# Sunrise.net
KiCad netlist of a schematic drawn in EAGLE
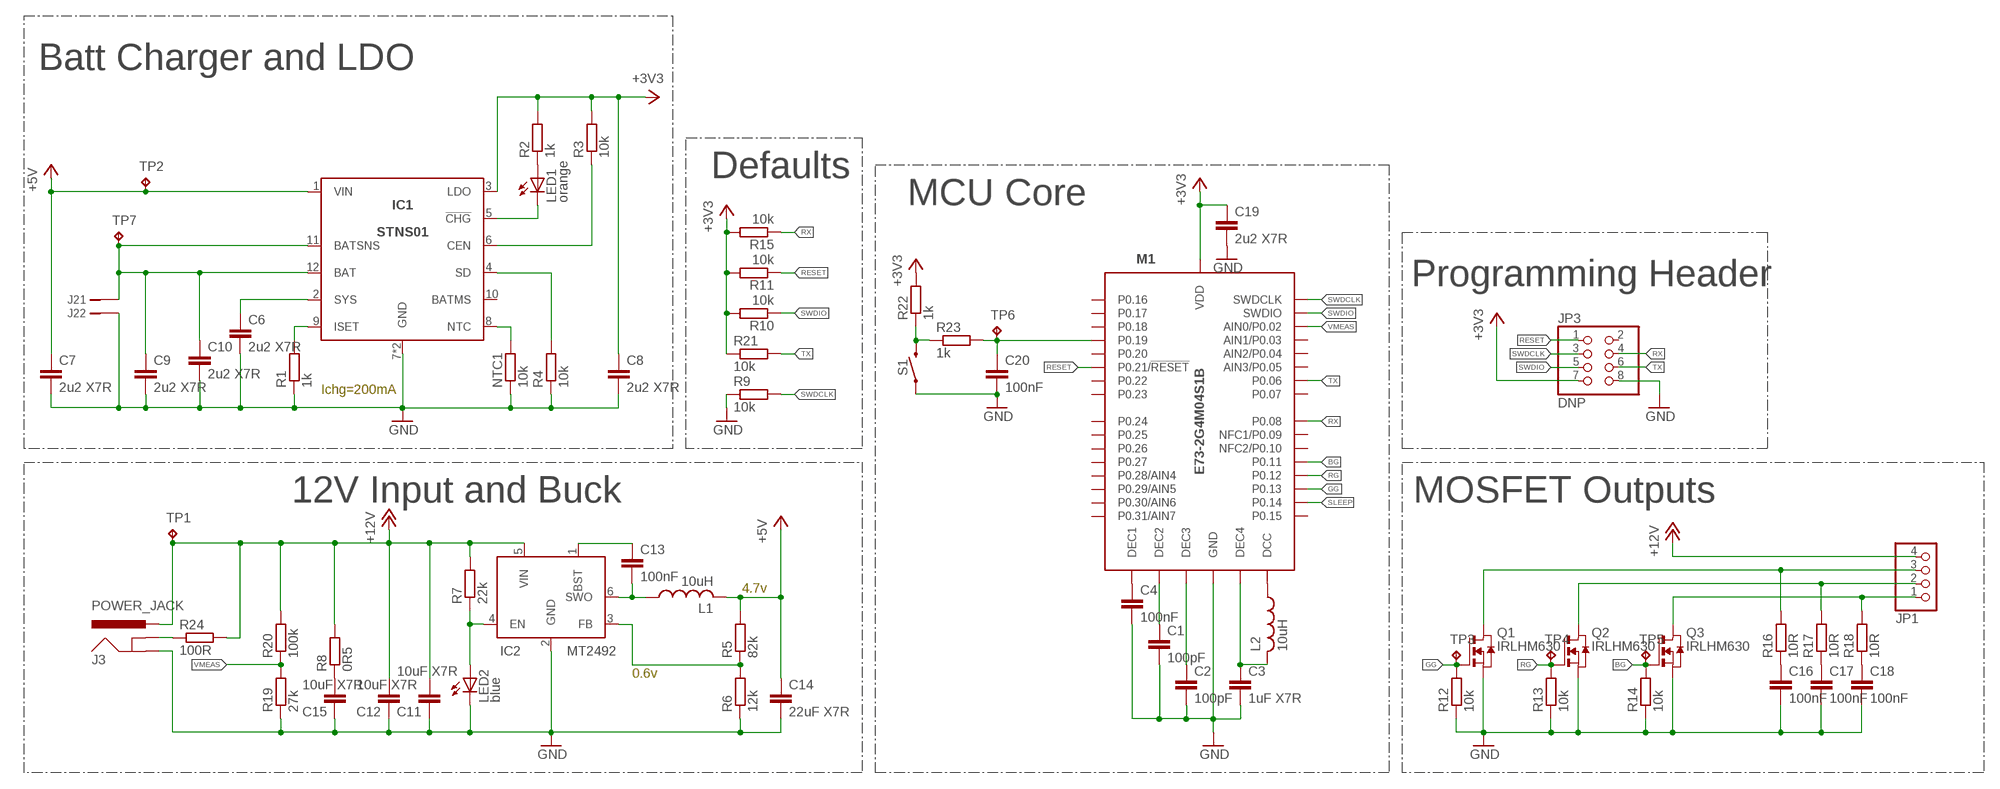
[diagram p0: schematic, sheet 1]

(export (version "E")
  (design (tool "Eeschema 10.0.6"))
  (components
    (comp (ref "C1")
      (value "100pF")
      (footprint "eagle-import:C0402K")
      (libsource (lib "eagle-import") (part "C-EUC0402K"))
    )
    (comp (ref "C2")
      (value "100pF")
      (footprint "eagle-import:C0402K")
      (libsource (lib "eagle-import") (part "C-EUC0402K"))
    )
    (comp (ref "C3")
      (value "1uF X7R")
      (footprint "eagle-import:C0603K")
      (libsource (lib "eagle-import") (part "C-EUC0603K"))
    )
    (comp (ref "C4")
      (value "100nF")
      (footprint "eagle-import:C0402K")
      (libsource (lib "eagle-import") (part "C-EUC0402K"))
    )
    (comp (ref "C6")
      (value "2u2 X7R")
      (footprint "eagle-import:C0603K")
      (libsource (lib "eagle-import") (part "C-EUC0603K"))
    )
    (comp (ref "C7")
      (value "2u2 X7R")
      (footprint "eagle-import:C0603K")
      (libsource (lib "eagle-import") (part "C-EUC0603K"))
    )
    (comp (ref "C8")
      (value "2u2 X7R")
      (footprint "eagle-import:C0603K")
      (libsource (lib "eagle-import") (part "C-EUC0603K"))
    )
    (comp (ref "C9")
      (value "2u2 X7R")
      (footprint "eagle-import:C0603K")
      (libsource (lib "eagle-import") (part "C-EUC0603K"))
    )
    (comp (ref "C10")
      (value "2u2 X7R")
      (footprint "eagle-import:C0603K")
      (libsource (lib "eagle-import") (part "C-EUC0603K"))
    )
    (comp (ref "C11")
      (value "10uF X7R")
      (footprint "eagle-import:C1206K")
      (libsource (lib "eagle-import") (part "C-EUC1206K"))
    )
    (comp (ref "C12")
      (value "10uF X7R")
      (footprint "eagle-import:C1206K")
      (libsource (lib "eagle-import") (part "C-EUC1206K"))
    )
    (comp (ref "C13")
      (value "100nF")
      (footprint "eagle-import:C0402K")
      (libsource (lib "eagle-import") (part "C-EUC0402K"))
    )
    (comp (ref "C14")
      (value "22uF X7R")
      (footprint "eagle-import:C1206K")
      (libsource (lib "eagle-import") (part "C-EUC1206K"))
    )
    (comp (ref "C15")
      (value "10uF X7R")
      (footprint "eagle-import:C1206K")
      (libsource (lib "eagle-import") (part "C-EUC1206K"))
    )
    (comp (ref "C16")
      (value "100nF")
      (footprint "eagle-import:C0402K")
      (libsource (lib "eagle-import") (part "C-EUC0402K"))
    )
    (comp (ref "C17")
      (value "100nF")
      (footprint "eagle-import:C0402K")
      (libsource (lib "eagle-import") (part "C-EUC0402K"))
    )
    (comp (ref "C18")
      (value "100nF")
      (footprint "eagle-import:C0402K")
      (libsource (lib "eagle-import") (part "C-EUC0402K"))
    )
    (comp (ref "C19")
      (value "2u2 X7R")
      (footprint "eagle-import:C0603K")
      (libsource (lib "eagle-import") (part "C-EUC0603K"))
    )
    (comp (ref "C20")
      (value "100nF")
      (footprint "eagle-import:C0402K")
      (libsource (lib "eagle-import") (part "C-EUC0402K"))
    )
    (comp (ref "IC1")
      (value "STNS01")
      (footprint "eagle-import:DFN12L-3MM")
      (fields (field (name "MF") "ST"))
      (libsource (lib "eagle-import") (part "STNS01"))
    )
    (comp (ref "IC2")
      (value "MT2492")
      (footprint "eagle-import:SOT23-6")
      (fields (field (name "MF") "Monolithic Power"))
      (libsource (lib "eagle-import") (part "MT2492"))
    )
    (comp (ref "J2")
      (value "B2B-PH-K-S")
      (footprint "eagle-import:B2B-PH-K-S")
      (fields (field (name "MF") "JST") (field (name "MPN") "B2B-PH-K-S"))
      (libsource (lib "eagle-import") (part "B2B-PH-K-S"))
    )
    (comp (ref "J3")
      (value "POWER_JACK")
      (footprint "eagle-import:POWER_JACK_PTH")
      (libsource (lib "eagle-import") (part "POWER_JACK"))
    )
    (comp (ref "JP1")
      (value "PINHD-1X4/90")
      (footprint "eagle-import:1X04_90")
      (libsource (lib "eagle-import") (part "PINHD-1X4/90"))
    )
    (comp (ref "JP3")
      (value "DNP")
      (footprint "eagle-import:2X04")
      (libsource (lib "eagle-import") (part "PINHD-2X4"))
    )
    (comp (ref "L1")
      (value "10uH")
      (footprint "eagle-import:2020-5050")
      (fields (field (name "MF") "Murata") (field (name "MPN") "LQH5BPN100MT0"))
      (libsource (lib "eagle-import") (part "INDUCTOR5050"))
    )
    (comp (ref "L2")
      (value "10uH")
      (footprint "eagle-import:0603-1608")
      (libsource (lib "eagle-import") (part "INDUCTOR1608"))
    )
    (comp (ref "LED1")
      (value "orange")
      (footprint "eagle-import:CHIP-LED0603")
      (libsource (lib "eagle-import") (part "LEDCHIP-LED0603"))
    )
    (comp (ref "LED2")
      (value "blue")
      (footprint "eagle-import:CHIP-LED0603")
      (libsource (lib "eagle-import") (part "LEDCHIP-LED0603"))
    )
    (comp (ref "M1")
      (value "E73-2G4M04S1B")
      (footprint "eagle-import:E73-2GM404S")
      (fields (field (name "MF") "Chengdu Ebyte") (field (name "MPN") "E7302G4M04S1B"))
      (libsource (lib "eagle-import") (part "E73-2G4M04S1B"))
    )
    (comp (ref "NTC1")
      (value "10k")
      (footprint "eagle-import:R0402")
      (libsource (lib "eagle-import") (part "R-EU_R0402"))
    )
    (comp (ref "Q1")
      (value "IRLHM630")
      (footprint "eagle-import:MLP8-33")
      (fields (field (name "MF") "International Rectifier") (field (name "MPN") "IRLHM630TRPbF"))
      (libsource (lib "eagle-import") (part "NMOS-MLP8-33"))
    )
    (comp (ref "Q2")
      (value "IRLHM630")
      (footprint "eagle-import:MLP8-33")
      (fields (field (name "MF") "International Rectifier") (field (name "MPN") "IRLHM630TRPbF"))
      (libsource (lib "eagle-import") (part "NMOS-MLP8-33"))
    )
    (comp (ref "Q3")
      (value "IRLHM630")
      (footprint "eagle-import:MLP8-33")
      (fields (field (name "MF") "International Rectifier") (field (name "MPN") "IRLHM630TRPbF"))
      (libsource (lib "eagle-import") (part "NMOS-MLP8-33"))
    )
    (comp (ref "R1")
      (value "1k")
      (footprint "eagle-import:R0402")
      (libsource (lib "eagle-import") (part "R-EU_R0402"))
    )
    (comp (ref "R2")
      (value "1k")
      (footprint "eagle-import:R0402")
      (libsource (lib "eagle-import") (part "R-EU_R0402"))
    )
    (comp (ref "R3")
      (value "10k")
      (footprint "eagle-import:R0402")
      (libsource (lib "eagle-import") (part "R-EU_R0402"))
    )
    (comp (ref "R4")
      (value "10k")
      (footprint "eagle-import:R0402")
      (libsource (lib "eagle-import") (part "R-EU_R0402"))
    )
    (comp (ref "R5")
      (value "82k")
      (footprint "eagle-import:R0402")
      (libsource (lib "eagle-import") (part "R-EU_R0402"))
    )
    (comp (ref "R6")
      (value "12k")
      (footprint "eagle-import:R0402")
      (libsource (lib "eagle-import") (part "R-EU_R0402"))
    )
    (comp (ref "R7")
      (value "22k")
      (footprint "eagle-import:R0402")
      (libsource (lib "eagle-import") (part "R-EU_R0402"))
    )
    (comp (ref "R8")
      (value "0R5")
      (footprint "eagle-import:R0402")
      (libsource (lib "eagle-import") (part "R-EU_R0402"))
    )
    (comp (ref "R9")
      (value "10k")
      (footprint "eagle-import:R0402")
      (libsource (lib "eagle-import") (part "R-EU_R0402"))
    )
    (comp (ref "R10")
      (value "10k")
      (footprint "eagle-import:R0402")
      (libsource (lib "eagle-import") (part "R-EU_R0402"))
    )
    (comp (ref "R11")
      (value "10k")
      (footprint "eagle-import:R0402")
      (libsource (lib "eagle-import") (part "R-EU_R0402"))
    )
    (comp (ref "R12")
      (value "10k")
      (footprint "eagle-import:R0402")
      (libsource (lib "eagle-import") (part "R-EU_R0402"))
    )
    (comp (ref "R13")
      (value "10k")
      (footprint "eagle-import:R0402")
      (libsource (lib "eagle-import") (part "R-EU_R0402"))
    )
    (comp (ref "R14")
      (value "10k")
      (footprint "eagle-import:R0402")
      (libsource (lib "eagle-import") (part "R-EU_R0402"))
    )
    (comp (ref "R15")
      (value "10k")
      (footprint "eagle-import:R0402")
      (libsource (lib "eagle-import") (part "R-EU_R0402"))
    )
    (comp (ref "R16")
      (value "10R")
      (footprint "eagle-import:R0402")
      (libsource (lib "eagle-import") (part "R-EU_R0402"))
    )
    (comp (ref "R17")
      (value "10R")
      (footprint "eagle-import:R0402")
      (libsource (lib "eagle-import") (part "R-EU_R0402"))
    )
    (comp (ref "R18")
      (value "10R")
      (footprint "eagle-import:R0402")
      (libsource (lib "eagle-import") (part "R-EU_R0402"))
    )
    (comp (ref "R19")
      (value "27k")
      (footprint "eagle-import:R0402")
      (libsource (lib "eagle-import") (part "R-EU_R0402"))
    )
    (comp (ref "R20")
      (value "100k")
      (footprint "eagle-import:R0402")
      (libsource (lib "eagle-import") (part "R-EU_R0402"))
    )
    (comp (ref "R21")
      (value "10k")
      (footprint "eagle-import:R0402")
      (libsource (lib "eagle-import") (part "R-EU_R0402"))
    )
    (comp (ref "R22")
      (value "1k")
      (footprint "eagle-import:R0402")
      (libsource (lib "eagle-import") (part "R-EU_R0402"))
    )
    (comp (ref "R23")
      (value "1k")
      (footprint "eagle-import:R0402")
      (libsource (lib "eagle-import") (part "R-EU_R0402"))
    )
    (comp (ref "R24")
      (value "100R")
      (footprint "eagle-import:R0402")
      (libsource (lib "eagle-import") (part "R-EU_R0402"))
    )
    (comp (ref "S1")
      (value "MOMENTARY-SWITCH-SPST-SMD-5.2MM")
      (footprint "eagle-import:TACTILE_SWITCH_SMD_5.2MM")
      (libsource (lib "eagle-import") (part "MOMENTARY-SWITCH-SPST-SMD-5.2MM"))
    )
    (comp (ref "TP1")
      (value "TPTP10R")
      (footprint "eagle-import:TP10R")
      (libsource (lib "eagle-import") (part "TPTP10R"))
    )
    (comp (ref "TP2")
      (value "TPTP10R")
      (footprint "eagle-import:TP10R")
      (libsource (lib "eagle-import") (part "TPTP10R"))
    )
    (comp (ref "TP3")
      (value "TPTP10R")
      (footprint "eagle-import:TP10R")
      (libsource (lib "eagle-import") (part "TPTP10R"))
    )
    (comp (ref "TP4")
      (value "TPTP10R")
      (footprint "eagle-import:TP10R")
      (libsource (lib "eagle-import") (part "TPTP10R"))
    )
    (comp (ref "TP5")
      (value "TPTP10R")
      (footprint "eagle-import:TP10R")
      (libsource (lib "eagle-import") (part "TPTP10R"))
    )
    (comp (ref "TP6")
      (value "TPTP10R")
      (footprint "eagle-import:TP10R")
      (libsource (lib "eagle-import") (part "TPTP10R"))
    )
    (comp (ref "TP7")
      (value "TPTP10R")
      (footprint "eagle-import:TP10R")
      (libsource (lib "eagle-import") (part "TPTP10R"))
    )
  )
  (nets
    (net (code "1") (name "+3V3") (class "Default")
      (node (ref "C19") (pin "1") (pinfunction "1_1") (pintype "passive"))
      (node (ref "C8") (pin "1") (pinfunction "1_1") (pintype "passive"))
      (node (ref "IC1") (pin "3") (pinfunction "LDO_3") (pintype "power_in"))
      (node (ref "JP3") (pin "7") (pinfunction "7_7") (pintype "passive"))
      (node (ref "M1") (pin "16") (pinfunction "VDD_16") (pintype "power_in"))
      (node (ref "R10") (pin "2") (pinfunction "2_2") (pintype "passive"))
      (node (ref "R11") (pin "2") (pinfunction "2_2") (pintype "passive"))
      (node (ref "R15") (pin "2") (pinfunction "2_2") (pintype "passive"))
      (node (ref "R2") (pin "2") (pinfunction "2_2") (pintype "passive"))
      (node (ref "R21") (pin "1") (pinfunction "1_1") (pintype "passive"))
      (node (ref "R22") (pin "2") (pinfunction "2_2") (pintype "passive"))
      (node (ref "R3") (pin "2") (pinfunction "2_2") (pintype "passive"))
    )
    (net (code "2") (name "+5V") (class "Default")
      (node (ref "C14") (pin "1") (pinfunction "1_1") (pintype "passive"))
      (node (ref "C7") (pin "1") (pinfunction "1_1") (pintype "passive"))
      (node (ref "IC1") (pin "1") (pinfunction "VIN_1") (pintype "power_in"))
      (node (ref "L1") (pin "2") (pinfunction "2_2") (pintype "passive"))
      (node (ref "R5") (pin "2") (pinfunction "2_2") (pintype "passive"))
      (node (ref "TP2") (pin "TP") (pinfunction "TP_TP") (pintype "input"))
    )
    (net (code "3") (name "+12V") (class "Default")
      (node (ref "C11") (pin "1") (pinfunction "1_1") (pintype "passive"))
      (node (ref "C12") (pin "1") (pinfunction "1_1") (pintype "passive"))
      (node (ref "IC2") (pin "5") (pinfunction "VIN_5") (pintype "power_in"))
      (node (ref "J3") (pin "PWR") (pinfunction "PWR_PWR") (pintype "bidirectional"))
      (node (ref "JP1") (pin "4") (pinfunction "4_4") (pintype "passive"))
      (node (ref "R20") (pin "2") (pinfunction "2_2") (pintype "passive"))
      (node (ref "R24") (pin "2") (pinfunction "2_2") (pintype "passive"))
      (node (ref "R7") (pin "2") (pinfunction "2_2") (pintype "passive"))
      (node (ref "R8") (pin "2") (pinfunction "2_2") (pintype "passive"))
      (node (ref "TP1") (pin "TP") (pinfunction "TP_TP") (pintype "input"))
    )
    (net (code "4") (name "BG") (class "Default")
      (node (ref "M1") (pin "26") (pinfunction "P0.11_26") (pintype "bidirectional"))
      (node (ref "Q3") (pin "GATE") (pinfunction "G_GATE") (pintype "passive"))
      (node (ref "R14") (pin "2") (pinfunction "2_2") (pintype "passive"))
      (node (ref "TP5") (pin "TP") (pinfunction "TP_TP") (pintype "input"))
    )
    (net (code "5") (name "GG") (class "Default")
      (node (ref "M1") (pin "28") (pinfunction "P0.13_28") (pintype "bidirectional"))
      (node (ref "Q1") (pin "GATE") (pinfunction "G_GATE") (pintype "passive"))
      (node (ref "R12") (pin "2") (pinfunction "2_2") (pintype "passive"))
      (node (ref "TP3") (pin "TP") (pinfunction "TP_TP") (pintype "input"))
    )
    (net (code "6") (name "GND") (class "Default")
      (node (ref "C1") (pin "2") (pinfunction "2_2") (pintype "passive"))
      (node (ref "C10") (pin "2") (pinfunction "2_2") (pintype "passive"))
      (node (ref "C11") (pin "2") (pinfunction "2_2") (pintype "passive"))
      (node (ref "C12") (pin "2") (pinfunction "2_2") (pintype "passive"))
      (node (ref "C14") (pin "2") (pinfunction "2_2") (pintype "passive"))
      (node (ref "C15") (pin "2") (pinfunction "2_2") (pintype "passive"))
      (node (ref "C16") (pin "2") (pinfunction "2_2") (pintype "passive"))
      (node (ref "C17") (pin "2") (pinfunction "2_2") (pintype "passive"))
      (node (ref "C18") (pin "2") (pinfunction "2_2") (pintype "passive"))
      (node (ref "C19") (pin "2") (pinfunction "2_2") (pintype "passive"))
      (node (ref "C2") (pin "2") (pinfunction "2_2") (pintype "passive"))
      (node (ref "C20") (pin "2") (pinfunction "2_2") (pintype "passive"))
      (node (ref "C3") (pin "2") (pinfunction "2_2") (pintype "passive"))
      (node (ref "C4") (pin "2") (pinfunction "2_2") (pintype "passive"))
      (node (ref "C6") (pin "2") (pinfunction "2_2") (pintype "passive"))
      (node (ref "C7") (pin "2") (pinfunction "2_2") (pintype "passive"))
      (node (ref "C8") (pin "2") (pinfunction "2_2") (pintype "passive"))
      (node (ref "C9") (pin "2") (pinfunction "2_2") (pintype "passive"))
      (node (ref "IC1") (pin "7") (pinfunction "GND_7") (pintype "power_in"))
      (node (ref "IC1") (pin "PAD") (pinfunction "GND_PAD") (pintype "power_in"))
      (node (ref "IC2") (pin "2") (pinfunction "GND_2") (pintype "power_in"))
      (node (ref "J2") (pin "2") (pinfunction "1_2") (pintype "passive"))
      (node (ref "J3") (pin "GND") (pinfunction "GND_GND") (pintype "bidirectional"))
      (node (ref "JP3") (pin "8") (pinfunction "8_8") (pintype "passive"))
      (node (ref "LED2") (pin "C") (pinfunction "C_C") (pintype "passive"))
      (node (ref "M1") (pin "0") (pinfunction "GND_0") (pintype "power_in"))
      (node (ref "M1") (pin "1") (pinfunction "GND_1") (pintype "power_in"))
      (node (ref "M1") (pin "15") (pinfunction "GND_15") (pintype "power_in"))
      (node (ref "M1") (pin "2") (pinfunction "GND_2") (pintype "power_in"))
      (node (ref "M1") (pin "42") (pinfunction "GND_42") (pintype "power_in"))
      (node (ref "M1") (pin "43") (pinfunction "GND_43") (pintype "power_in"))
      (node (ref "NTC1") (pin "1") (pinfunction "1_1") (pintype "passive"))
      (node (ref "Q1") (pin "S1") (pinfunction "S_S1") (pintype "passive"))
      (node (ref "Q1") (pin "S2") (pinfunction "S_S2") (pintype "passive"))
      (node (ref "Q1") (pin "S3") (pinfunction "S_S3") (pintype "passive"))
      (node (ref "Q2") (pin "S1") (pinfunction "S_S1") (pintype "passive"))
      (node (ref "Q2") (pin "S2") (pinfunction "S_S2") (pintype "passive"))
      (node (ref "Q2") (pin "S3") (pinfunction "S_S3") (pintype "passive"))
      (node (ref "Q3") (pin "S1") (pinfunction "S_S1") (pintype "passive"))
      (node (ref "Q3") (pin "S2") (pinfunction "S_S2") (pintype "passive"))
      (node (ref "Q3") (pin "S3") (pinfunction "S_S3") (pintype "passive"))
      (node (ref "R1") (pin "1") (pinfunction "1_1") (pintype "passive"))
      (node (ref "R12") (pin "1") (pinfunction "1_1") (pintype "passive"))
      (node (ref "R13") (pin "1") (pinfunction "1_1") (pintype "passive"))
      (node (ref "R14") (pin "1") (pinfunction "1_1") (pintype "passive"))
      (node (ref "R19") (pin "1") (pinfunction "1_1") (pintype "passive"))
      (node (ref "R4") (pin "1") (pinfunction "1_1") (pintype "passive"))
      (node (ref "R6") (pin "1") (pinfunction "1_1") (pintype "passive"))
      (node (ref "R9") (pin "1") (pinfunction "1_1") (pintype "passive"))
      (node (ref "S1") (pin "1") (pinfunction "1_1") (pintype "passive"))
    )
    (net (code "7") (name "Net-(C15-Pad1)") (class "Default")
      (node (ref "C15") (pin "1") (pinfunction "1_1") (pintype "passive"))
      (node (ref "R8") (pin "1") (pinfunction "1_1") (pintype "passive"))
    )
    (net (code "8") (name "Net-(C16-Pad1)") (class "Default")
      (node (ref "C16") (pin "1") (pinfunction "1_1") (pintype "passive"))
      (node (ref "R16") (pin "1") (pinfunction "1_1") (pintype "passive"))
    )
    (net (code "9") (name "Net-(C17-Pad1)") (class "Default")
      (node (ref "C17") (pin "1") (pinfunction "1_1") (pintype "passive"))
      (node (ref "R17") (pin "1") (pinfunction "1_1") (pintype "passive"))
    )
    (net (code "10") (name "Net-(C18-Pad1)") (class "Default")
      (node (ref "C18") (pin "1") (pinfunction "1_1") (pintype "passive"))
      (node (ref "R18") (pin "1") (pinfunction "1_1") (pintype "passive"))
    )
    (net (code "11") (name "Net-(IC1-BAT)") (class "Default")
      (node (ref "C10") (pin "1") (pinfunction "1_1") (pintype "passive"))
      (node (ref "C9") (pin "1") (pinfunction "1_1") (pintype "passive"))
      (node (ref "IC1") (pin "11") (pinfunction "BATSNS_11") (pintype "bidirectional"))
      (node (ref "IC1") (pin "12") (pinfunction "BAT_12") (pintype "bidirectional"))
      (node (ref "J2") (pin "1") (pinfunction "1_1") (pintype "passive"))
      (node (ref "TP7") (pin "TP") (pinfunction "TP_TP") (pintype "input"))
    )
    (net (code "12") (name "Net-(IC1-CEN)") (class "Default")
      (node (ref "IC1") (pin "6") (pinfunction "CEN_6") (pintype "bidirectional"))
      (node (ref "R3") (pin "1") (pinfunction "1_1") (pintype "passive"))
    )
    (net (code "13") (name "Net-(IC1-ISET)") (class "Default")
      (node (ref "IC1") (pin "9") (pinfunction "ISET_9") (pintype "bidirectional"))
      (node (ref "R1") (pin "2") (pinfunction "2_2") (pintype "passive"))
    )
    (net (code "14") (name "Net-(IC1-NTC)") (class "Default")
      (node (ref "IC1") (pin "8") (pinfunction "NTC_8") (pintype "bidirectional"))
      (node (ref "NTC1") (pin "2") (pinfunction "2_2") (pintype "passive"))
    )
    (net (code "15") (name "Net-(IC1-SD)") (class "Default")
      (node (ref "IC1") (pin "4") (pinfunction "SD_4") (pintype "bidirectional"))
      (node (ref "R4") (pin "2") (pinfunction "2_2") (pintype "passive"))
    )
    (net (code "16") (name "Net-(IC1-SYS)") (class "Default")
      (node (ref "C6") (pin "1") (pinfunction "1_1") (pintype "passive"))
      (node (ref "IC1") (pin "2") (pinfunction "SYS_2") (pintype "bidirectional"))
    )
    (net (code "17") (name "Net-(IC1-~{CHG})") (class "Default")
      (node (ref "IC1") (pin "5") (pinfunction "~{CHG}_5") (pintype "bidirectional"))
      (node (ref "LED1") (pin "C") (pinfunction "C_C") (pintype "passive"))
    )
    (net (code "18") (name "Net-(IC2-BST)") (class "Default")
      (node (ref "C13") (pin "1") (pinfunction "1_1") (pintype "passive"))
      (node (ref "IC2") (pin "1") (pinfunction "BST_1") (pintype "input"))
    )
    (net (code "19") (name "Net-(IC2-EN)") (class "Default")
      (node (ref "IC2") (pin "4") (pinfunction "EN_4") (pintype "input"))
      (node (ref "LED2") (pin "A") (pinfunction "A_A") (pintype "passive"))
      (node (ref "R7") (pin "1") (pinfunction "1_1") (pintype "passive"))
    )
    (net (code "20") (name "Net-(IC2-FB)") (class "Default")
      (node (ref "IC2") (pin "3") (pinfunction "FB_3") (pintype "input"))
      (node (ref "R5") (pin "1") (pinfunction "1_1") (pintype "passive"))
      (node (ref "R6") (pin "2") (pinfunction "2_2") (pintype "passive"))
    )
    (net (code "21") (name "Net-(IC2-SWO)") (class "Default")
      (node (ref "C13") (pin "2") (pinfunction "2_2") (pintype "passive"))
      (node (ref "IC2") (pin "6") (pinfunction "SWO_6") (pintype "output"))
      (node (ref "L1") (pin "1") (pinfunction "1_1") (pintype "passive"))
    )
    (net (code "22") (name "Net-(J3-PadGNDBREAK)") (class "Default")
      (node (ref "J3") (pin "GNDBREAK") (pinfunction "GNDBREAK_GNDBREAK") (pintype "bidirectional"))
      (node (ref "R24") (pin "1") (pinfunction "1_1") (pintype "passive"))
    )
    (net (code "23") (name "Net-(JP1-Pad1)") (class "Default")
      (node (ref "JP1") (pin "1") (pinfunction "1_1") (pintype "passive"))
      (node (ref "Q3") (pin "D1") (pinfunction "D_D1") (pintype "passive"))
      (node (ref "Q3") (pin "D2") (pinfunction "D_D2") (pintype "passive"))
      (node (ref "Q3") (pin "D3") (pinfunction "D_D3") (pintype "passive"))
      (node (ref "Q3") (pin "D4") (pinfunction "D_D4") (pintype "passive"))
      (node (ref "Q3") (pin "DRAIN0") (pinfunction "D_DRAIN0") (pintype "passive"))
      (node (ref "R18") (pin "2") (pinfunction "2_2") (pintype "passive"))
    )
    (net (code "24") (name "Net-(JP1-Pad2)") (class "Default")
      (node (ref "JP1") (pin "2") (pinfunction "2_2") (pintype "passive"))
      (node (ref "Q2") (pin "D1") (pinfunction "D_D1") (pintype "passive"))
      (node (ref "Q2") (pin "D2") (pinfunction "D_D2") (pintype "passive"))
      (node (ref "Q2") (pin "D3") (pinfunction "D_D3") (pintype "passive"))
      (node (ref "Q2") (pin "D4") (pinfunction "D_D4") (pintype "passive"))
      (node (ref "Q2") (pin "DRAIN0") (pinfunction "D_DRAIN0") (pintype "passive"))
      (node (ref "R17") (pin "2") (pinfunction "2_2") (pintype "passive"))
    )
    (net (code "25") (name "Net-(JP1-Pad3)") (class "Default")
      (node (ref "JP1") (pin "3") (pinfunction "3_3") (pintype "passive"))
      (node (ref "Q1") (pin "D1") (pinfunction "D_D1") (pintype "passive"))
      (node (ref "Q1") (pin "D2") (pinfunction "D_D2") (pintype "passive"))
      (node (ref "Q1") (pin "D3") (pinfunction "D_D3") (pintype "passive"))
      (node (ref "Q1") (pin "D4") (pinfunction "D_D4") (pintype "passive"))
      (node (ref "Q1") (pin "DRAIN0") (pinfunction "D_DRAIN0") (pintype "passive"))
      (node (ref "R16") (pin "2") (pinfunction "2_2") (pintype "passive"))
    )
    (net (code "26") (name "Net-(LED1-PadA)") (class "Default")
      (node (ref "LED1") (pin "A") (pinfunction "A_A") (pintype "passive"))
      (node (ref "R2") (pin "1") (pinfunction "1_1") (pintype "passive"))
    )
    (net (code "27") (name "Net-(M1-DCC)") (class "Default")
      (node (ref "L2") (pin "1") (pinfunction "1_1") (pintype "passive"))
      (node (ref "M1") (pin "13") (pinfunction "DCC_13") (pintype "bidirectional"))
    )
    (net (code "28") (name "Net-(M1-DEC1)") (class "Default")
      (node (ref "C4") (pin "1") (pinfunction "1_1") (pintype "passive"))
      (node (ref "M1") (pin "14") (pinfunction "DEC1_14") (pintype "bidirectional"))
    )
    (net (code "29") (name "Net-(M1-DEC2)") (class "Default")
      (node (ref "C1") (pin "1") (pinfunction "1_1") (pintype "passive"))
      (node (ref "M1") (pin "3") (pinfunction "DEC2_3") (pintype "bidirectional"))
    )
    (net (code "30") (name "Net-(M1-DEC3)") (class "Default")
      (node (ref "C2") (pin "1") (pinfunction "1_1") (pintype "passive"))
      (node (ref "M1") (pin "4") (pinfunction "DEC3_4") (pintype "bidirectional"))
    )
    (net (code "31") (name "Net-(M1-DEC4)") (class "Default")
      (node (ref "C3") (pin "1") (pinfunction "1_1") (pintype "passive"))
      (node (ref "L2") (pin "2") (pinfunction "2_2") (pintype "passive"))
      (node (ref "M1") (pin "12") (pinfunction "DEC4_12") (pintype "bidirectional"))
    )
    (net (code "32") (name "Net-(M1-P0.19)") (class "Default")
      (node (ref "C20") (pin "1") (pinfunction "1_1") (pintype "passive"))
      (node (ref "M1") (pin "34") (pinfunction "P0.19_34") (pintype "bidirectional"))
      (node (ref "R23") (pin "2") (pinfunction "2_2") (pintype "passive"))
      (node (ref "TP6") (pin "TP") (pinfunction "TP_TP") (pintype "input"))
    )
    (net (code "33") (name "Net-(S1-2)") (class "Default")
      (node (ref "R22") (pin "1") (pinfunction "1_1") (pintype "passive"))
      (node (ref "R23") (pin "1") (pinfunction "1_1") (pintype "passive"))
      (node (ref "S1") (pin "3") (pinfunction "2_3") (pintype "passive"))
    )
    (net (code "34") (name "RESET") (class "Default")
      (node (ref "JP3") (pin "1") (pinfunction "1_1") (pintype "passive"))
      (node (ref "M1") (pin "36") (pinfunction "P0.21/~{RESET}_36") (pintype "bidirectional"))
      (node (ref "R11") (pin "1") (pinfunction "1_1") (pintype "passive"))
    )
    (net (code "35") (name "RG") (class "Default")
      (node (ref "M1") (pin "27") (pinfunction "P0.12_27") (pintype "bidirectional"))
      (node (ref "Q2") (pin "GATE") (pinfunction "G_GATE") (pintype "passive"))
      (node (ref "R13") (pin "2") (pinfunction "2_2") (pintype "passive"))
      (node (ref "TP4") (pin "TP") (pinfunction "TP_TP") (pintype "input"))
    )
    (net (code "36") (name "RX") (class "Default")
      (node (ref "JP3") (pin "4") (pinfunction "4_4") (pintype "passive"))
      (node (ref "M1") (pin "23") (pinfunction "P0.08_23") (pintype "bidirectional"))
      (node (ref "R15") (pin "1") (pinfunction "1_1") (pintype "passive"))
    )
    (net (code "37") (name "SLEEP") (class "Default")
      (node (ref "M1") (pin "29") (pinfunction "P0.14_29") (pintype "bidirectional"))
    )
    (net (code "38") (name "SWDCLK") (class "Default")
      (node (ref "JP3") (pin "3") (pinfunction "3_3") (pintype "passive"))
      (node (ref "M1") (pin "37") (pinfunction "SWDCLK_37") (pintype "input"))
      (node (ref "R9") (pin "2") (pinfunction "2_2") (pintype "passive"))
    )
    (net (code "39") (name "SWDIO") (class "Default")
      (node (ref "JP3") (pin "5") (pinfunction "5_5") (pintype "passive"))
      (node (ref "M1") (pin "38") (pinfunction "SWDIO_38") (pintype "bidirectional"))
      (node (ref "R10") (pin "1") (pinfunction "1_1") (pintype "passive"))
    )
    (net (code "40") (name "TX") (class "Default")
      (node (ref "JP3") (pin "6") (pinfunction "6_6") (pintype "passive"))
      (node (ref "M1") (pin "21") (pinfunction "P0.06_21") (pintype "bidirectional"))
      (node (ref "R21") (pin "2") (pinfunction "2_2") (pintype "passive"))
    )
    (net (code "41") (name "VMEAS") (class "Default")
      (node (ref "M1") (pin "17") (pinfunction "AIN0/P0.02_17") (pintype "bidirectional"))
      (node (ref "R19") (pin "2") (pinfunction "2_2") (pintype "passive"))
      (node (ref "R20") (pin "1") (pinfunction "1_1") (pintype "passive"))
    )
    (net (code "42") (name "unconnected-(IC1-BATMS-Pad10)") (class "Default")
      (node (ref "IC1") (pin "10") (pinfunction "BATMS_10") (pintype "bidirectional"))
    )
    (net (code "43") (name "unconnected-(JP3-Pad2)") (class "Default")
      (node (ref "JP3") (pin "2") (pinfunction "2_2") (pintype "passive"))
    )
    (net (code "44") (name "unconnected-(M1-AIN1{slash}P0.03-Pad18)") (class "Default")
      (node (ref "M1") (pin "18") (pinfunction "AIN1/P0.03_18") (pintype "bidirectional"))
    )
    (net (code "45") (name "unconnected-(M1-AIN2{slash}P0.04-Pad19)") (class "Default")
      (node (ref "M1") (pin "19") (pinfunction "AIN2/P0.04_19") (pintype "bidirectional"))
    )
    (net (code "46") (name "unconnected-(M1-AIN3{slash}P0.05-Pad20)") (class "Default")
      (node (ref "M1") (pin "20") (pinfunction "AIN3/P0.05_20") (pintype "bidirectional"))
    )
    (net (code "47") (name "unconnected-(M1-NFC1{slash}P0.09-Pad24)") (class "Default")
      (node (ref "M1") (pin "24") (pinfunction "NFC1/P0.09_24") (pintype "bidirectional"))
    )
    (net (code "48") (name "unconnected-(M1-NFC2{slash}P0.10-Pad25)") (class "Default")
      (node (ref "M1") (pin "25") (pinfunction "NFC2/P0.10_25") (pintype "bidirectional"))
    )
    (net (code "49") (name "unconnected-(M1-P0.07-Pad22)") (class "Default")
      (node (ref "M1") (pin "22") (pinfunction "P0.07_22") (pintype "bidirectional"))
    )
    (net (code "50") (name "unconnected-(M1-P0.15-Pad30)") (class "Default")
      (node (ref "M1") (pin "30") (pinfunction "P0.15_30") (pintype "bidirectional"))
    )
    (net (code "51") (name "unconnected-(M1-P0.16-Pad31)") (class "Default")
      (node (ref "M1") (pin "31") (pinfunction "P0.16_31") (pintype "bidirectional"))
    )
    (net (code "52") (name "unconnected-(M1-P0.17-Pad32)") (class "Default")
      (node (ref "M1") (pin "32") (pinfunction "P0.17_32") (pintype "bidirectional"))
    )
    (net (code "53") (name "unconnected-(M1-P0.18-Pad33)") (class "Default")
      (node (ref "M1") (pin "33") (pinfunction "P0.18_33") (pintype "bidirectional"))
    )
    (net (code "54") (name "unconnected-(M1-P0.20-Pad35)") (class "Default")
      (node (ref "M1") (pin "35") (pinfunction "P0.20_35") (pintype "bidirectional"))
    )
    (net (code "55") (name "unconnected-(M1-P0.22-Pad39)") (class "Default")
      (node (ref "M1") (pin "39") (pinfunction "P0.22_39") (pintype "bidirectional"))
    )
    (net (code "56") (name "unconnected-(M1-P0.23-Pad40)") (class "Default")
      (node (ref "M1") (pin "40") (pinfunction "P0.23_40") (pintype "bidirectional"))
    )
    (net (code "57") (name "unconnected-(M1-P0.24-Pad41)") (class "Default")
      (node (ref "M1") (pin "41") (pinfunction "P0.24_41") (pintype "bidirectional"))
    )
    (net (code "58") (name "unconnected-(M1-P0.25-Pad5)") (class "Default")
      (node (ref "M1") (pin "5") (pinfunction "P0.25_5") (pintype "bidirectional"))
    )
    (net (code "59") (name "unconnected-(M1-P0.26-Pad6)") (class "Default")
      (node (ref "M1") (pin "6") (pinfunction "P0.26_6") (pintype "bidirectional"))
    )
    (net (code "60") (name "unconnected-(M1-P0.27-Pad7)") (class "Default")
      (node (ref "M1") (pin "7") (pinfunction "P0.27_7") (pintype "bidirectional"))
    )
    (net (code "61") (name "unconnected-(M1-P0.28{slash}AIN4-Pad8)") (class "Default")
      (node (ref "M1") (pin "8") (pinfunction "P0.28/AIN4_8") (pintype "bidirectional"))
    )
    (net (code "62") (name "unconnected-(M1-P0.29{slash}AIN5-Pad9)") (class "Default")
      (node (ref "M1") (pin "9") (pinfunction "P0.29/AIN5_9") (pintype "bidirectional"))
    )
    (net (code "63") (name "unconnected-(M1-P0.30{slash}AIN6-Pad10)") (class "Default")
      (node (ref "M1") (pin "10") (pinfunction "P0.30/AIN6_10") (pintype "bidirectional"))
    )
    (net (code "64") (name "unconnected-(M1-P0.31{slash}AIN7-Pad11)") (class "Default")
      (node (ref "M1") (pin "11") (pinfunction "P0.31/AIN7_11") (pintype "bidirectional"))
    )
  )
)
